# usb328.net
KiCad netlist of a schematic drawn in EAGLE
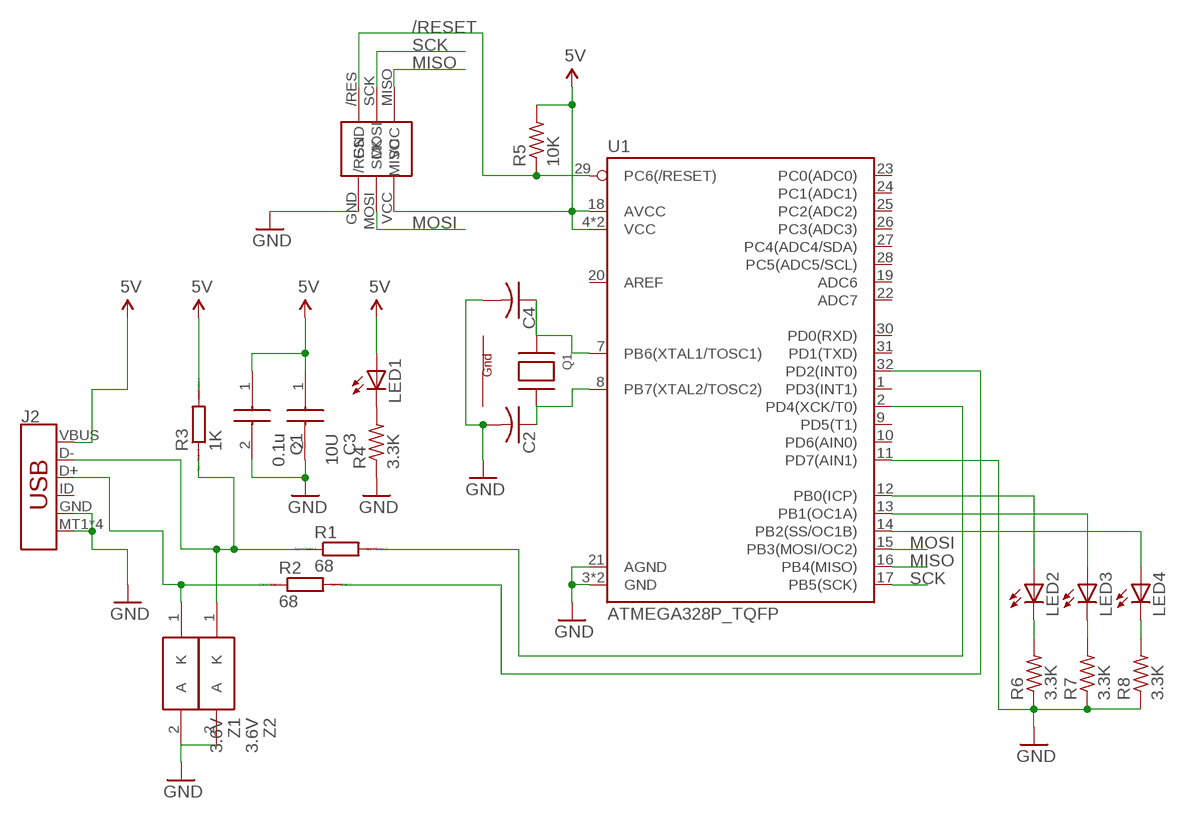
[diagram p0: schematic, sheet 1]

(export (version "E")
  (design (tool "Eeschema 10.0.6"))
  (components
    (comp (ref "C1")
      (value "0.1u")
      (footprint "eagle-import:CAPC2012X70N")
      (fields
        (field (name "ARROW_PART_NUMBER") "GRM2165C1H220JZ01D")
        (field (name "RS_PART_NUMBER") "7236243")
      )
      (libsource (lib "eagle-import") (part "GRM2165C1H220JZ01D"))
    )
    (comp (ref "C2")
      (value "C-USC0805")
      (footprint "eagle-import:C0805")
      (libsource (lib "eagle-import") (part "C-USC0805"))
    )
    (comp (ref "C3")
      (value "10U")
      (footprint "eagle-import:CAPC2012X70N")
      (fields
        (field (name "ARROW_PART_NUMBER") "GRM2165C1H220JZ01D")
        (field (name "RS_PART_NUMBER") "7236243")
      )
      (libsource (lib "eagle-import") (part "GRM2165C1H220JZ01D"))
    )
    (comp (ref "C4")
      (value "C-USC0805")
      (footprint "eagle-import:C0805")
      (libsource (lib "eagle-import") (part "C-USC0805"))
    )
    (comp (ref "J2")
      (value "USB_MICRO-B_SMT")
      (footprint "eagle-import:USB-MICROB")
      (libsource (lib "eagle-import") (part "USB_MICRO-B_SMT"))
    )
    (comp (ref "LED1")
      (value "LEDCHIPLED_0805")
      (footprint "eagle-import:CHIPLED_0805")
      (libsource (lib "eagle-import") (part "LEDCHIPLED_0805"))
    )
    (comp (ref "LED2")
      (value "LEDCHIPLED_0805")
      (footprint "eagle-import:CHIPLED_0805")
      (libsource (lib "eagle-import") (part "LEDCHIPLED_0805"))
    )
    (comp (ref "LED3")
      (value "LEDCHIPLED_0805")
      (footprint "eagle-import:CHIPLED_0805")
      (libsource (lib "eagle-import") (part "LEDCHIPLED_0805"))
    )
    (comp (ref "LED4")
      (value "LEDCHIPLED_0805")
      (footprint "eagle-import:CHIPLED_0805")
      (libsource (lib "eagle-import") (part "LEDCHIPLED_0805"))
    )
    (comp (ref "Q1")
      (value "XTAL-4-3225")
      (footprint "eagle-import:NX3225")
      (libsource (lib "eagle-import") (part "XTAL-4-3225"))
    )
    (comp (ref "R1")
      (value "68")
      (footprint "eagle-import:R2012")
      (libsource (lib "eagle-import") (part "RR2012"))
    )
    (comp (ref "R2")
      (value "68")
      (footprint "eagle-import:R2012")
      (libsource (lib "eagle-import") (part "RR2012"))
    )
    (comp (ref "R3")
      (value "1K")
      (footprint "eagle-import:R2012")
      (libsource (lib "eagle-import") (part "RR2012"))
    )
    (comp (ref "R4")
      (value "3.3K")
      (footprint "eagle-import:R0805")
      (libsource (lib "eagle-import") (part "R-US_R0805"))
    )
    (comp (ref "R5")
      (value "10K")
      (footprint "eagle-import:R0805")
      (libsource (lib "eagle-import") (part "R-US_R0805"))
    )
    (comp (ref "R6")
      (value "3.3K")
      (footprint "eagle-import:R0805")
      (libsource (lib "eagle-import") (part "R-US_R0805"))
    )
    (comp (ref "R7")
      (value "3.3K")
      (footprint "eagle-import:R0805")
      (libsource (lib "eagle-import") (part "R-US_R0805"))
    )
    (comp (ref "R8")
      (value "3.3K")
      (footprint "eagle-import:R0805")
      (libsource (lib "eagle-import") (part "R-US_R0805"))
    )
    (comp (ref "U$4")
      (value "ICSP-E")
      (footprint "eagle-import:ICSP-E")
      (libsource (lib "eagle-import") (part "ICSP-E"))
    )
    (comp (ref "U1")
      (value "ATMEGA328P_TQFP")
      (footprint "eagle-import:TQFP32-08")
      (libsource (lib "eagle-import") (part "ATMEGA328P_TQFP"))
    )
    (comp (ref "Z1")
      (value "3.6V")
      (footprint "eagle-import:TUM-D2")
      (fields (field (name "ARROW_PART_NUMBER") "TFZVTR15B") (field (name "RS_PART_NUMBER") "1715293"))
      (libsource (lib "eagle-import") (part "TFZVTR15B"))
    )
    (comp (ref "Z2")
      (value "3.6V")
      (footprint "eagle-import:TUM-D2")
      (fields (field (name "ARROW_PART_NUMBER") "TFZVTR15B") (field (name "RS_PART_NUMBER") "1715293"))
      (libsource (lib "eagle-import") (part "TFZVTR15B"))
    )
  )
  (nets
    (net (code "1") (name "/G1") (class "Default")
      (node (ref "Q1") (pin "4") (pinfunction "G1_4") (pintype "power_in"))
    )
    (net (code "2") (name "/G2") (class "Default")
      (node (ref "Q1") (pin "2") (pinfunction "G2_2") (pintype "power_in"))
    )
    (net (code "3") (name "/MISO") (class "Default")
      (node (ref "U$4") (pin "MISO") (pinfunction "MISO_MISO") (pintype "bidirectional"))
      (node (ref "U1") (pin "16") (pinfunction "PB4(MISO)_16") (pintype "bidirectional"))
    )
    (net (code "4") (name "/MOSI") (class "Default")
      (node (ref "U$4") (pin "MOSI") (pinfunction "MOSI_MOSI") (pintype "bidirectional"))
      (node (ref "U1") (pin "15") (pinfunction "PB3(MOSI/OC2)_15") (pintype "bidirectional"))
    )
    (net (code "5") (name "/SCK") (class "Default")
      (node (ref "U$4") (pin "SCK") (pinfunction "SCK_SCK") (pintype "bidirectional"))
      (node (ref "U1") (pin "17") (pinfunction "PB5(SCK)_17") (pintype "bidirectional"))
    )
    (net (code "6") (name "/{slash}RESET") (class "Default")
      (node (ref "R5") (pin "1") (pinfunction "1_1") (pintype "passive"))
      (node (ref "U$4") (pin "/RES") (pinfunction "/RES_/RES") (pintype "bidirectional"))
      (node (ref "U1") (pin "29") (pinfunction "PC6(/RESET)_29") (pintype "bidirectional"))
    )
    (net (code "7") (name "5V") (class "Default")
      (node (ref "C1") (pin "1") (pinfunction "1_1") (pintype "bidirectional"))
      (node (ref "C3") (pin "1") (pinfunction "1_1") (pintype "bidirectional"))
      (node (ref "J2") (pin "VBUS") (pinfunction "VBUS_VBUS") (pintype "power_in"))
      (node (ref "LED1") (pin "A") (pinfunction "A_A") (pintype "passive"))
      (node (ref "R3") (pin "2") (pinfunction "2_2") (pintype "passive"))
      (node (ref "R5") (pin "2") (pinfunction "2_2") (pintype "passive"))
      (node (ref "U$4") (pin "VCC") (pinfunction "VCC_VCC") (pintype "bidirectional"))
      (node (ref "U1") (pin "18") (pinfunction "AVCC_18") (pintype "bidirectional"))
      (node (ref "U1") (pin "4") (pinfunction "VCC_4") (pintype "bidirectional"))
      (node (ref "U1") (pin "6") (pinfunction "VCC_6") (pintype "bidirectional"))
    )
    (net (code "8") (name "GND") (class "Default")
      (node (ref "C1") (pin "2") (pinfunction "2_2") (pintype "bidirectional"))
      (node (ref "C2") (pin "2") (pinfunction "2_2") (pintype "passive"))
      (node (ref "C3") (pin "2") (pinfunction "2_2") (pintype "bidirectional"))
      (node (ref "C4") (pin "2") (pinfunction "2_2") (pintype "passive"))
      (node (ref "J2") (pin "GND") (pinfunction "GND_GND") (pintype "power_in"))
      (node (ref "J2") (pin "MT1") (pinfunction "SHIELD_MT1") (pintype "bidirectional"))
      (node (ref "J2") (pin "MT2") (pinfunction "SHIELD_MT2") (pintype "bidirectional"))
      (node (ref "J2") (pin "P$1") (pinfunction "SHIELD_P$1") (pintype "bidirectional"))
      (node (ref "J2") (pin "P$2") (pinfunction "SHIELD_P$2") (pintype "bidirectional"))
      (node (ref "R4") (pin "1") (pinfunction "1_1") (pintype "passive"))
      (node (ref "R6") (pin "1") (pinfunction "1_1") (pintype "passive"))
      (node (ref "R7") (pin "1") (pinfunction "1_1") (pintype "passive"))
      (node (ref "R8") (pin "1") (pinfunction "1_1") (pintype "passive"))
      (node (ref "U$4") (pin "GND") (pinfunction "GND_GND") (pintype "bidirectional"))
      (node (ref "U1") (pin "11") (pinfunction "PD7(AIN1)_11") (pintype "bidirectional"))
      (node (ref "U1") (pin "21") (pinfunction "AGND_21") (pintype "bidirectional"))
      (node (ref "U1") (pin "3") (pinfunction "GND_3") (pintype "bidirectional"))
      (node (ref "U1") (pin "5") (pinfunction "GND_5") (pintype "bidirectional"))
      (node (ref "Z1") (pin "2") (pinfunction "A_2") (pintype "bidirectional"))
      (node (ref "Z2") (pin "2") (pinfunction "A_2") (pintype "bidirectional"))
    )
    (net (code "9") (name "Net-(LED1-PadC)") (class "Default")
      (node (ref "LED1") (pin "C") (pinfunction "C_C") (pintype "passive"))
      (node (ref "R4") (pin "2") (pinfunction "2_2") (pintype "passive"))
    )
    (net (code "10") (name "Net-(LED2-PadC)") (class "Default")
      (node (ref "LED2") (pin "C") (pinfunction "C_C") (pintype "passive"))
      (node (ref "R6") (pin "2") (pinfunction "2_2") (pintype "passive"))
    )
    (net (code "11") (name "Net-(LED3-PadC)") (class "Default")
      (node (ref "LED3") (pin "C") (pinfunction "C_C") (pintype "passive"))
      (node (ref "R7") (pin "2") (pinfunction "2_2") (pintype "passive"))
    )
    (net (code "12") (name "Net-(LED4-PadC)") (class "Default")
      (node (ref "LED4") (pin "C") (pinfunction "C_C") (pintype "passive"))
      (node (ref "R8") (pin "2") (pinfunction "2_2") (pintype "passive"))
    )
    (net (code "13") (name "Net-(Q1-X1)") (class "Default")
      (node (ref "C4") (pin "1") (pinfunction "1_1") (pintype "passive"))
      (node (ref "Q1") (pin "1") (pinfunction "X1_1") (pintype "bidirectional"))
      (node (ref "U1") (pin "7") (pinfunction "PB6(XTAL1/TOSC1)_7") (pintype "bidirectional"))
    )
    (net (code "14") (name "Net-(Q1-X2)") (class "Default")
      (node (ref "C2") (pin "1") (pinfunction "1_1") (pintype "passive"))
      (node (ref "Q1") (pin "3") (pinfunction "X2_3") (pintype "bidirectional"))
      (node (ref "U1") (pin "8") (pinfunction "PB7(XTAL2/TOSC2)_8") (pintype "bidirectional"))
    )
    (net (code "15") (name "Net-(U1-PB0(ICP))") (class "Default")
      (node (ref "LED2") (pin "A") (pinfunction "A_A") (pintype "passive"))
      (node (ref "U1") (pin "12") (pinfunction "PB0(ICP)_12") (pintype "bidirectional"))
    )
    (net (code "16") (name "Net-(U1-PB1(OC1A))") (class "Default")
      (node (ref "LED3") (pin "A") (pinfunction "A_A") (pintype "passive"))
      (node (ref "U1") (pin "13") (pinfunction "PB1(OC1A)_13") (pintype "bidirectional"))
    )
    (net (code "17") (name "Net-(U1-PB2(SS{slash}OC1B))") (class "Default")
      (node (ref "LED4") (pin "A") (pinfunction "A_A") (pintype "passive"))
      (node (ref "U1") (pin "14") (pinfunction "PB2(SS/OC1B)_14") (pintype "bidirectional"))
    )
    (net (code "18") (name "Net-(U1-PD2(INT0))") (class "Default")
      (node (ref "R2") (pin "2") (pinfunction "2_2") (pintype "passive"))
      (node (ref "U1") (pin "32") (pinfunction "PD2(INT0)_32") (pintype "bidirectional"))
    )
    (net (code "19") (name "Net-(U1-PD4(XCK{slash}T0))") (class "Default")
      (node (ref "R1") (pin "2") (pinfunction "2_2") (pintype "passive"))
      (node (ref "U1") (pin "2") (pinfunction "PD4(XCK/T0)_2") (pintype "bidirectional"))
    )
    (net (code "20") (name "Net-(Z1-K)") (class "Default")
      (node (ref "J2") (pin "D+") (pinfunction "D+_D+") (pintype "bidirectional"))
      (node (ref "R2") (pin "1") (pinfunction "1_1") (pintype "passive"))
      (node (ref "Z1") (pin "1") (pinfunction "K_1") (pintype "bidirectional"))
    )
    (net (code "21") (name "Net-(Z2-K)") (class "Default")
      (node (ref "J2") (pin "D-") (pinfunction "D-_D-") (pintype "bidirectional"))
      (node (ref "R1") (pin "1") (pinfunction "1_1") (pintype "passive"))
      (node (ref "R3") (pin "1") (pinfunction "1_1") (pintype "passive"))
      (node (ref "Z2") (pin "1") (pinfunction "K_1") (pintype "bidirectional"))
    )
    (net (code "22") (name "unconnected-(J2-PadID)") (class "Default")
      (node (ref "J2") (pin "ID") (pinfunction "ID_ID") (pintype "bidirectional"))
    )
    (net (code "23") (name "unconnected-(U1-ADC6-Pad19)") (class "Default")
      (node (ref "U1") (pin "19") (pinfunction "ADC6_19") (pintype "bidirectional"))
    )
    (net (code "24") (name "unconnected-(U1-ADC7-Pad22)") (class "Default")
      (node (ref "U1") (pin "22") (pinfunction "ADC7_22") (pintype "bidirectional"))
    )
    (net (code "25") (name "unconnected-(U1-AREF-Pad20)") (class "Default")
      (node (ref "U1") (pin "20") (pinfunction "AREF_20") (pintype "bidirectional"))
    )
    (net (code "26") (name "unconnected-(U1-PC0(ADC0)-Pad23)") (class "Default")
      (node (ref "U1") (pin "23") (pinfunction "PC0(ADC0)_23") (pintype "bidirectional"))
    )
    (net (code "27") (name "unconnected-(U1-PC1(ADC1)-Pad24)") (class "Default")
      (node (ref "U1") (pin "24") (pinfunction "PC1(ADC1)_24") (pintype "bidirectional"))
    )
    (net (code "28") (name "unconnected-(U1-PC2(ADC2)-Pad25)") (class "Default")
      (node (ref "U1") (pin "25") (pinfunction "PC2(ADC2)_25") (pintype "bidirectional"))
    )
    (net (code "29") (name "unconnected-(U1-PC3(ADC3)-Pad26)") (class "Default")
      (node (ref "U1") (pin "26") (pinfunction "PC3(ADC3)_26") (pintype "bidirectional"))
    )
    (net (code "30") (name "unconnected-(U1-PC4(ADC4{slash}SDA)-Pad27)") (class "Default")
      (node (ref "U1") (pin "27") (pinfunction "PC4(ADC4/SDA)_27") (pintype "bidirectional"))
    )
    (net (code "31") (name "unconnected-(U1-PC5(ADC5{slash}SCL)-Pad28)") (class "Default")
      (node (ref "U1") (pin "28") (pinfunction "PC5(ADC5/SCL)_28") (pintype "bidirectional"))
    )
    (net (code "32") (name "unconnected-(U1-PD0(RXD)-Pad30)") (class "Default")
      (node (ref "U1") (pin "30") (pinfunction "PD0(RXD)_30") (pintype "bidirectional"))
    )
    (net (code "33") (name "unconnected-(U1-PD1(TXD)-Pad31)") (class "Default")
      (node (ref "U1") (pin "31") (pinfunction "PD1(TXD)_31") (pintype "bidirectional"))
    )
    (net (code "34") (name "unconnected-(U1-PD3(INT1)-Pad1)") (class "Default")
      (node (ref "U1") (pin "1") (pinfunction "PD3(INT1)_1") (pintype "bidirectional"))
    )
    (net (code "35") (name "unconnected-(U1-PD5(T1)-Pad9)") (class "Default")
      (node (ref "U1") (pin "9") (pinfunction "PD5(T1)_9") (pintype "bidirectional"))
    )
    (net (code "36") (name "unconnected-(U1-PD6(AIN0)-Pad10)") (class "Default")
      (node (ref "U1") (pin "10") (pinfunction "PD6(AIN0)_10") (pintype "bidirectional"))
    )
  )
)
